# SCH_macropad-pcb_2024-06-17.net
KiCad netlist of a schematic drawn in EasyEDA
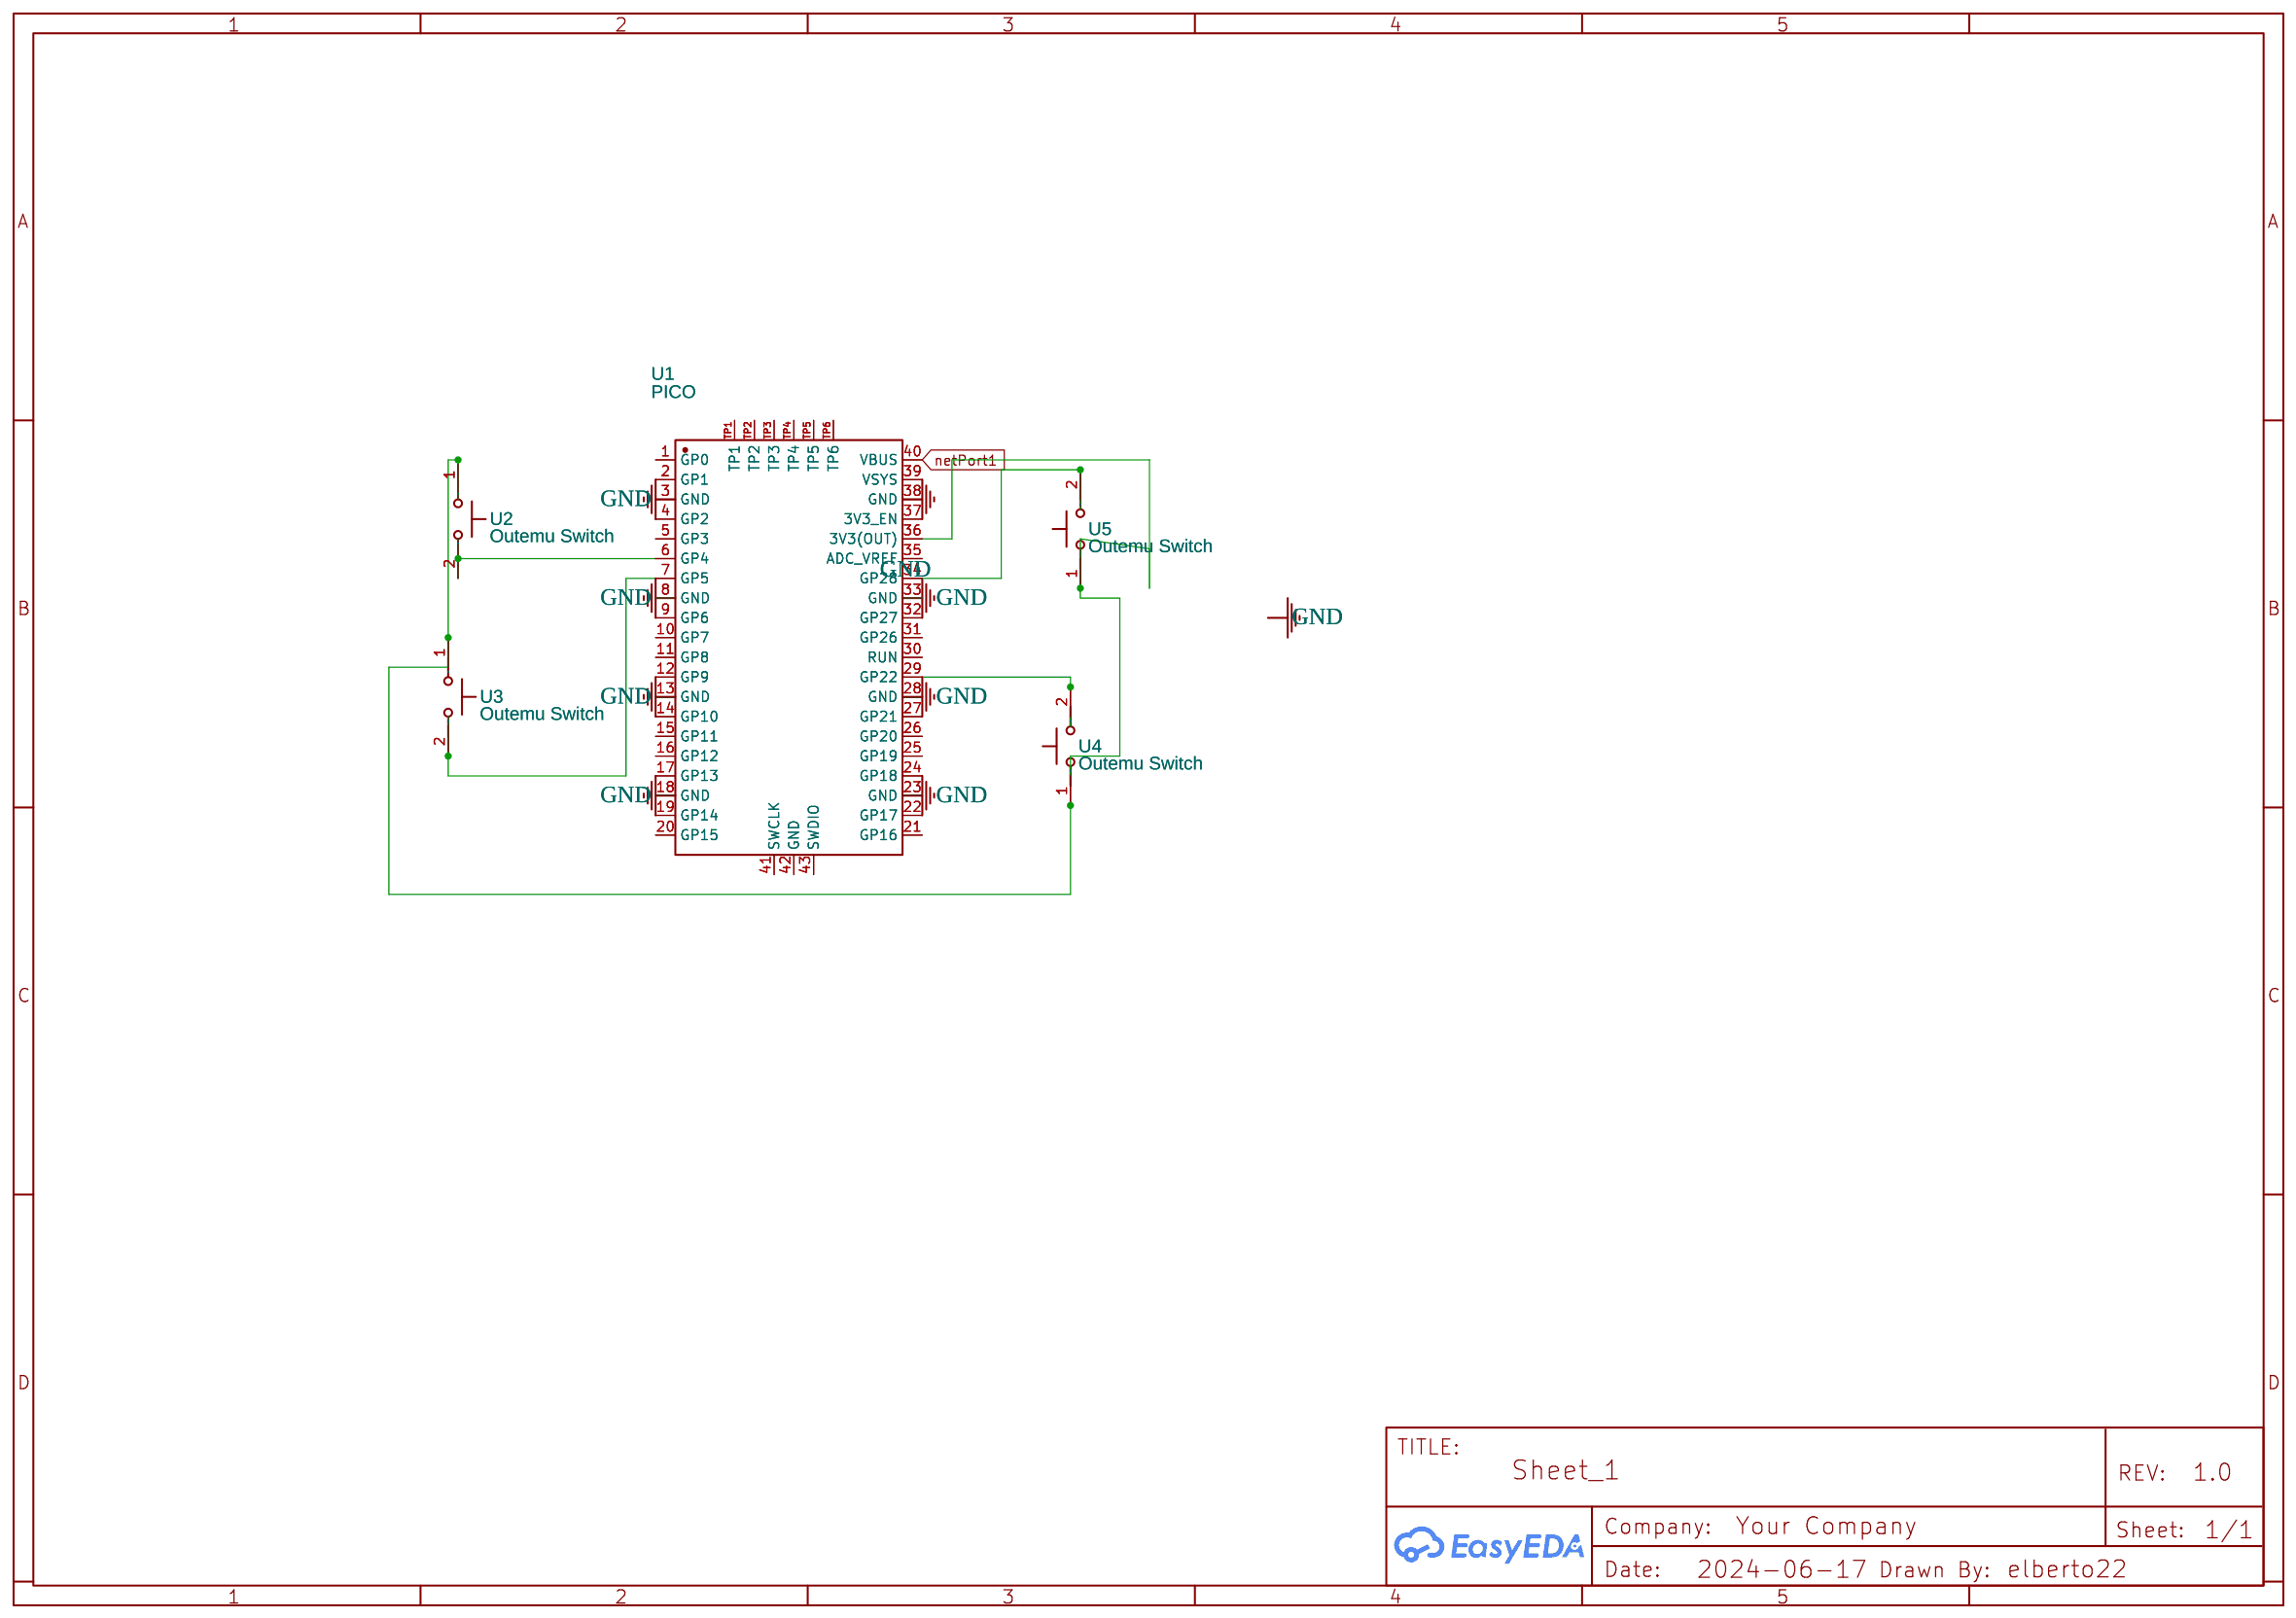
[diagram p0: schematic sheet]

(export (version "E")
  (design (tool "Eeschema 10.0.6"))
  (components
    (comp (ref "U1")
      (value "PICO")
      (fields (field (name "Manufacturer") "Raspberry Pi(树莓派)"))
      (libsource (lib "") (part "PICO"))
    )
    (comp (ref "U2")
      (value "Outemu Switch")
      (fields (field (name "Manufacturer") "HepLer"))
      (libsource (lib "") (part "Outemu Switch_1"))
    )
    (comp (ref "U3")
      (value "Outemu Switch")
      (fields (field (name "Manufacturer") "HepLer"))
      (libsource (lib "") (part "Outemu Switch_1"))
    )
    (comp (ref "U4")
      (value "Outemu Switch")
      (fields (field (name "Manufacturer") "HepLer"))
      (libsource (lib "") (part "Outemu Switch"))
    )
    (comp (ref "U5")
      (value "Outemu Switch")
      (fields (field (name "Manufacturer") "HepLer"))
      (libsource (lib "") (part "Outemu Switch"))
    )
  )
  (nets
    (net (code "1") (name "GND") (class "Default")
      (node (ref "U1") (pin "13") (pinfunction "GND_13") (pintype "unspecified"))
      (node (ref "U1") (pin "18") (pinfunction "GND_18") (pintype "unspecified"))
      (node (ref "U1") (pin "23") (pinfunction "GND_23") (pintype "unspecified"))
      (node (ref "U1") (pin "28") (pinfunction "GND_28") (pintype "unspecified"))
      (node (ref "U1") (pin "33") (pinfunction "GND_33") (pintype "unspecified"))
      (node (ref "U1") (pin "8") (pinfunction "GND_8") (pintype "unspecified"))
    )
    (net (code "2") (name "Net-(U1-3V3(OUT))") (class "Default")
      (node (ref "U1") (pin "36") (pinfunction "3V3(OUT)_36") (pintype "unspecified"))
      (node (ref "U2") (pin "1") (pinfunction "1_1") (pintype "unspecified"))
      (node (ref "U3") (pin "1") (pinfunction "1_1") (pintype "unspecified"))
      (node (ref "U4") (pin "1") (pinfunction "1_1") (pintype "unspecified"))
      (node (ref "U5") (pin "1") (pinfunction "1_1") (pintype "unspecified"))
    )
    (net (code "3") (name "Net-(U1-GP4)") (class "Default")
      (node (ref "U1") (pin "6") (pinfunction "GP4_6") (pintype "unspecified"))
      (node (ref "U2") (pin "2") (pinfunction "2_2") (pintype "unspecified"))
    )
    (net (code "4") (name "Net-(U1-GP5)") (class "Default")
      (node (ref "U1") (pin "7") (pinfunction "GP5_7") (pintype "unspecified"))
      (node (ref "U3") (pin "2") (pinfunction "2_2") (pintype "unspecified"))
    )
    (net (code "5") (name "Net-(U1-GP22)") (class "Default")
      (node (ref "U1") (pin "29") (pinfunction "GP22_29") (pintype "unspecified"))
      (node (ref "U4") (pin "2") (pinfunction "2_2") (pintype "unspecified"))
    )
    (net (code "6") (name "Net-(U1-GP28)") (class "Default")
      (node (ref "U1") (pin "34") (pinfunction "GP28_34") (pintype "unspecified"))
      (node (ref "U5") (pin "2") (pinfunction "2_2") (pintype "unspecified"))
    )
    (net (code "7") (name "netPort1") (class "Default")
      (node (ref "U1") (pin "40") (pinfunction "VBUS_40") (pintype "unspecified"))
    )
    (net (code "8") (name "unconnected-(U1-3V3_EN-Pad37)") (class "Default")
      (node (ref "U1") (pin "37") (pinfunction "3V3_EN_37") (pintype "unspecified"))
    )
    (net (code "9") (name "unconnected-(U1-ADC_VREF-Pad35)") (class "Default")
      (node (ref "U1") (pin "35") (pinfunction "ADC_VREF_35") (pintype "unspecified"))
    )
    (net (code "10") (name "unconnected-(U1-GND-Pad3)") (class "Default")
      (node (ref "U1") (pin "3") (pinfunction "GND_3") (pintype "unspecified"))
    )
    (net (code "11") (name "unconnected-(U1-GND-Pad38)") (class "Default")
      (node (ref "U1") (pin "38") (pinfunction "GND_38") (pintype "unspecified"))
    )
    (net (code "12") (name "unconnected-(U1-GND-Pad42)") (class "Default")
      (node (ref "U1") (pin "42") (pinfunction "GND_42") (pintype "unspecified"))
    )
    (net (code "13") (name "unconnected-(U1-GP0-Pad1)") (class "Default")
      (node (ref "U1") (pin "1") (pinfunction "GP0_1") (pintype "unspecified"))
    )
    (net (code "14") (name "unconnected-(U1-GP1-Pad2)") (class "Default")
      (node (ref "U1") (pin "2") (pinfunction "GP1_2") (pintype "unspecified"))
    )
    (net (code "15") (name "unconnected-(U1-GP2-Pad4)") (class "Default")
      (node (ref "U1") (pin "4") (pinfunction "GP2_4") (pintype "unspecified"))
    )
    (net (code "16") (name "unconnected-(U1-GP3-Pad5)") (class "Default")
      (node (ref "U1") (pin "5") (pinfunction "GP3_5") (pintype "unspecified"))
    )
    (net (code "17") (name "unconnected-(U1-GP6-Pad9)") (class "Default")
      (node (ref "U1") (pin "9") (pinfunction "GP6_9") (pintype "unspecified"))
    )
    (net (code "18") (name "unconnected-(U1-GP7-Pad10)") (class "Default")
      (node (ref "U1") (pin "10") (pinfunction "GP7_10") (pintype "unspecified"))
    )
    (net (code "19") (name "unconnected-(U1-GP8-Pad11)") (class "Default")
      (node (ref "U1") (pin "11") (pinfunction "GP8_11") (pintype "unspecified"))
    )
    (net (code "20") (name "unconnected-(U1-GP9-Pad12)") (class "Default")
      (node (ref "U1") (pin "12") (pinfunction "GP9_12") (pintype "unspecified"))
    )
    (net (code "21") (name "unconnected-(U1-GP10-Pad14)") (class "Default")
      (node (ref "U1") (pin "14") (pinfunction "GP10_14") (pintype "unspecified"))
    )
    (net (code "22") (name "unconnected-(U1-GP11-Pad15)") (class "Default")
      (node (ref "U1") (pin "15") (pinfunction "GP11_15") (pintype "unspecified"))
    )
    (net (code "23") (name "unconnected-(U1-GP12-Pad16)") (class "Default")
      (node (ref "U1") (pin "16") (pinfunction "GP12_16") (pintype "unspecified"))
    )
    (net (code "24") (name "unconnected-(U1-GP13-Pad17)") (class "Default")
      (node (ref "U1") (pin "17") (pinfunction "GP13_17") (pintype "unspecified"))
    )
    (net (code "25") (name "unconnected-(U1-GP14-Pad19)") (class "Default")
      (node (ref "U1") (pin "19") (pinfunction "GP14_19") (pintype "unspecified"))
    )
    (net (code "26") (name "unconnected-(U1-GP15-Pad20)") (class "Default")
      (node (ref "U1") (pin "20") (pinfunction "GP15_20") (pintype "unspecified"))
    )
    (net (code "27") (name "unconnected-(U1-GP16-Pad21)") (class "Default")
      (node (ref "U1") (pin "21") (pinfunction "GP16_21") (pintype "unspecified"))
    )
    (net (code "28") (name "unconnected-(U1-GP17-Pad22)") (class "Default")
      (node (ref "U1") (pin "22") (pinfunction "GP17_22") (pintype "unspecified"))
    )
    (net (code "29") (name "unconnected-(U1-GP18-Pad24)") (class "Default")
      (node (ref "U1") (pin "24") (pinfunction "GP18_24") (pintype "unspecified"))
    )
    (net (code "30") (name "unconnected-(U1-GP19-Pad25)") (class "Default")
      (node (ref "U1") (pin "25") (pinfunction "GP19_25") (pintype "unspecified"))
    )
    (net (code "31") (name "unconnected-(U1-GP20-Pad26)") (class "Default")
      (node (ref "U1") (pin "26") (pinfunction "GP20_26") (pintype "unspecified"))
    )
    (net (code "32") (name "unconnected-(U1-GP21-Pad27)") (class "Default")
      (node (ref "U1") (pin "27") (pinfunction "GP21_27") (pintype "unspecified"))
    )
    (net (code "33") (name "unconnected-(U1-GP26-Pad31)") (class "Default")
      (node (ref "U1") (pin "31") (pinfunction "GP26_31") (pintype "unspecified"))
    )
    (net (code "34") (name "unconnected-(U1-GP27-Pad32)") (class "Default")
      (node (ref "U1") (pin "32") (pinfunction "GP27_32") (pintype "unspecified"))
    )
    (net (code "35") (name "unconnected-(U1-PadTP1)") (class "Default")
      (node (ref "U1") (pin "TP1") (pinfunction "TP1_TP1") (pintype "unspecified"))
    )
    (net (code "36") (name "unconnected-(U1-PadTP2)") (class "Default")
      (node (ref "U1") (pin "TP2") (pinfunction "TP2_TP2") (pintype "unspecified"))
    )
    (net (code "37") (name "unconnected-(U1-PadTP3)") (class "Default")
      (node (ref "U1") (pin "TP3") (pinfunction "TP3_TP3") (pintype "unspecified"))
    )
    (net (code "38") (name "unconnected-(U1-PadTP4)") (class "Default")
      (node (ref "U1") (pin "TP4") (pinfunction "TP4_TP4") (pintype "unspecified"))
    )
    (net (code "39") (name "unconnected-(U1-PadTP5)") (class "Default")
      (node (ref "U1") (pin "TP5") (pinfunction "TP5_TP5") (pintype "unspecified"))
    )
    (net (code "40") (name "unconnected-(U1-PadTP6)") (class "Default")
      (node (ref "U1") (pin "TP6") (pinfunction "TP6_TP6") (pintype "unspecified"))
    )
    (net (code "41") (name "unconnected-(U1-RUN-Pad30)") (class "Default")
      (node (ref "U1") (pin "30") (pinfunction "RUN_30") (pintype "unspecified"))
    )
    (net (code "42") (name "unconnected-(U1-SWCLK-Pad41)") (class "Default")
      (node (ref "U1") (pin "41") (pinfunction "SWCLK_41") (pintype "unspecified"))
    )
    (net (code "43") (name "unconnected-(U1-SWDIO-Pad43)") (class "Default")
      (node (ref "U1") (pin "43") (pinfunction "SWDIO_43") (pintype "unspecified"))
    )
    (net (code "44") (name "unconnected-(U1-VSYS-Pad39)") (class "Default")
      (node (ref "U1") (pin "39") (pinfunction "VSYS_39") (pintype "unspecified"))
    )
  )
)
